# STIM300-carrierboard.net
KiCad netlist of a schematic drawn in Altium Designer
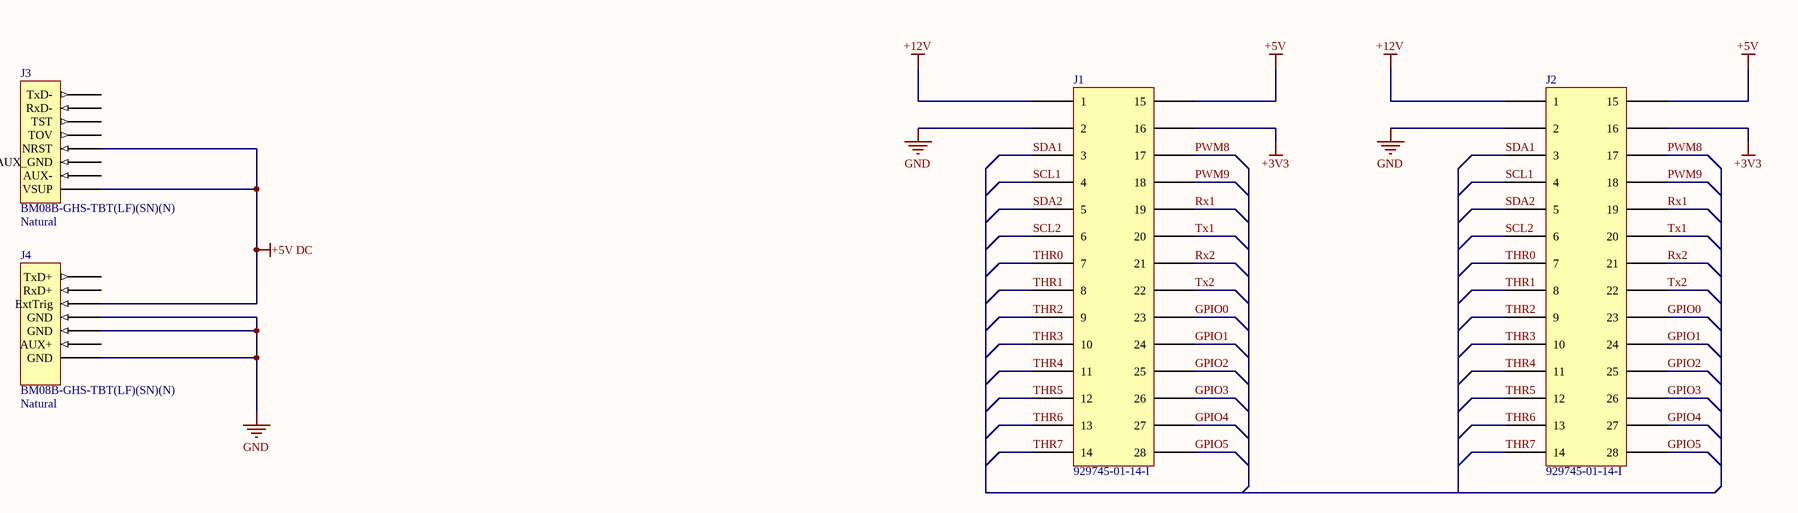
[diagram p0: STIM300-carrierboard.SchDoc]

(export (version "E")
  (design (tool "Eeschema 10.0.6"))
  (components
    (comp (ref "J1")
      (value "929745-01-14-I")
      (footprint "Header_14x2_RA")
      (libsource (lib "Vortex-component-database") (part "Header 14x2 RA"))
    )
    (comp (ref "J2")
      (value "929745-01-14-I")
      (footprint "Header_14x2_RA")
      (libsource (lib "Vortex-component-database") (part "Header 14x2 RA"))
    )
    (comp (ref "J3")
      (value "BM08B-GHS-TBT(LF)(SN)(N)")
      (footprint "JST BM08B-GHS-TBT")
      (description "CONN HEADER GH TOP 8POS 1.25MM")
      (fields (field (name "COLOUR") "Natural") (field (name "MANUFACTURER") "JST Sales America Inc."))
      (libsource (lib "Celestial Library Database") (part "8 Pin"))
    )
    (comp (ref "J4")
      (value "BM08B-GHS-TBT(LF)(SN)(N)")
      (footprint "JST BM08B-GHS-TBT")
      (description "CONN HEADER GH TOP 8POS 1.25MM")
      (fields (field (name "COLOUR") "Natural") (field (name "MANUFACTURER") "JST Sales America Inc."))
      (libsource (lib "Celestial Library Database") (part "8 Pin"))
    )
  )
  (nets
    (net (code "1") (name "+3V3") (class "Default")
      (node (ref "J1") (pin "16") (pinfunction "16_16") (pintype "passive"))
      (node (ref "J2") (pin "16") (pinfunction "16_16") (pintype "passive"))
    )
    (net (code "2") (name "+5V") (class "Default")
      (node (ref "J1") (pin "15") (pinfunction "15_15") (pintype "passive"))
      (node (ref "J2") (pin "15") (pinfunction "15_15") (pintype "passive"))
    )
    (net (code "3") (name "+5V DC") (class "Default")
      (node (ref "J3") (pin "5") (pinfunction "NRST_5") (pintype "input"))
      (node (ref "J3") (pin "8") (pinfunction "VSUP_8") (pintype "power_in"))
      (node (ref "J4") (pin "3") (pinfunction "TST_3") (pintype "output"))
    )
    (net (code "4") (name "+12V") (class "Default")
      (node (ref "J1") (pin "1") (pinfunction "1_1") (pintype "passive"))
      (node (ref "J2") (pin "1") (pinfunction "1_1") (pintype "passive"))
    )
    (net (code "5") (name "/GPIO0") (class "Default")
      (node (ref "J1") (pin "23") (pinfunction "23_23") (pintype "passive"))
      (node (ref "J2") (pin "23") (pinfunction "23_23") (pintype "passive"))
    )
    (net (code "6") (name "/GPIO1") (class "Default")
      (node (ref "J1") (pin "24") (pinfunction "24_24") (pintype "passive"))
      (node (ref "J2") (pin "24") (pinfunction "24_24") (pintype "passive"))
    )
    (net (code "7") (name "/GPIO2") (class "Default")
      (node (ref "J1") (pin "25") (pinfunction "25_25") (pintype "passive"))
      (node (ref "J2") (pin "25") (pinfunction "25_25") (pintype "passive"))
    )
    (net (code "8") (name "/GPIO3") (class "Default")
      (node (ref "J1") (pin "26") (pinfunction "26_26") (pintype "passive"))
      (node (ref "J2") (pin "26") (pinfunction "26_26") (pintype "passive"))
    )
    (net (code "9") (name "/GPIO4") (class "Default")
      (node (ref "J1") (pin "27") (pinfunction "27_27") (pintype "passive"))
      (node (ref "J2") (pin "27") (pinfunction "27_27") (pintype "passive"))
    )
    (net (code "10") (name "/GPIO5") (class "Default")
      (node (ref "J1") (pin "28") (pinfunction "28_28") (pintype "passive"))
      (node (ref "J2") (pin "28") (pinfunction "28_28") (pintype "passive"))
    )
    (net (code "11") (name "/PWM8") (class "Default")
      (node (ref "J1") (pin "17") (pinfunction "17_17") (pintype "passive"))
      (node (ref "J2") (pin "17") (pinfunction "17_17") (pintype "passive"))
    )
    (net (code "12") (name "/PWM9") (class "Default")
      (node (ref "J1") (pin "18") (pinfunction "18_18") (pintype "passive"))
      (node (ref "J2") (pin "18") (pinfunction "18_18") (pintype "passive"))
    )
    (net (code "13") (name "/Rx1") (class "Default")
      (node (ref "J1") (pin "19") (pinfunction "19_19") (pintype "passive"))
      (node (ref "J2") (pin "19") (pinfunction "19_19") (pintype "passive"))
    )
    (net (code "14") (name "/Rx2") (class "Default")
      (node (ref "J1") (pin "21") (pinfunction "21_21") (pintype "passive"))
      (node (ref "J2") (pin "21") (pinfunction "21_21") (pintype "passive"))
    )
    (net (code "15") (name "/SCL1") (class "Default")
      (node (ref "J1") (pin "4") (pinfunction "4_4") (pintype "passive"))
      (node (ref "J2") (pin "4") (pinfunction "4_4") (pintype "passive"))
    )
    (net (code "16") (name "/SCL2") (class "Default")
      (node (ref "J1") (pin "6") (pinfunction "6_6") (pintype "passive"))
      (node (ref "J2") (pin "6") (pinfunction "6_6") (pintype "passive"))
    )
    (net (code "17") (name "/SDA1") (class "Default")
      (node (ref "J1") (pin "3") (pinfunction "3_3") (pintype "passive"))
      (node (ref "J2") (pin "3") (pinfunction "3_3") (pintype "passive"))
    )
    (net (code "18") (name "/SDA2") (class "Default")
      (node (ref "J1") (pin "5") (pinfunction "5_5") (pintype "passive"))
      (node (ref "J2") (pin "5") (pinfunction "5_5") (pintype "passive"))
    )
    (net (code "19") (name "/THR0") (class "Default")
      (node (ref "J1") (pin "7") (pinfunction "7_7") (pintype "passive"))
      (node (ref "J2") (pin "7") (pinfunction "7_7") (pintype "passive"))
    )
    (net (code "20") (name "/THR1") (class "Default")
      (node (ref "J1") (pin "8") (pinfunction "8_8") (pintype "passive"))
      (node (ref "J2") (pin "8") (pinfunction "8_8") (pintype "passive"))
    )
    (net (code "21") (name "/THR2") (class "Default")
      (node (ref "J1") (pin "9") (pinfunction "9_9") (pintype "passive"))
      (node (ref "J2") (pin "9") (pinfunction "9_9") (pintype "passive"))
    )
    (net (code "22") (name "/THR3") (class "Default")
      (node (ref "J1") (pin "10") (pinfunction "10_10") (pintype "passive"))
      (node (ref "J2") (pin "10") (pinfunction "10_10") (pintype "passive"))
    )
    (net (code "23") (name "/THR4") (class "Default")
      (node (ref "J1") (pin "11") (pinfunction "11_11") (pintype "passive"))
      (node (ref "J2") (pin "11") (pinfunction "11_11") (pintype "passive"))
    )
    (net (code "24") (name "/THR5") (class "Default")
      (node (ref "J1") (pin "12") (pinfunction "12_12") (pintype "passive"))
      (node (ref "J2") (pin "12") (pinfunction "12_12") (pintype "passive"))
    )
    (net (code "25") (name "/THR6") (class "Default")
      (node (ref "J1") (pin "13") (pinfunction "13_13") (pintype "passive"))
      (node (ref "J2") (pin "13") (pinfunction "13_13") (pintype "passive"))
    )
    (net (code "26") (name "/THR7") (class "Default")
      (node (ref "J1") (pin "14") (pinfunction "14_14") (pintype "passive"))
      (node (ref "J2") (pin "14") (pinfunction "14_14") (pintype "passive"))
    )
    (net (code "27") (name "/Tx1") (class "Default")
      (node (ref "J1") (pin "20") (pinfunction "20_20") (pintype "passive"))
      (node (ref "J2") (pin "20") (pinfunction "20_20") (pintype "passive"))
    )
    (net (code "28") (name "/Tx2") (class "Default")
      (node (ref "J1") (pin "22") (pinfunction "22_22") (pintype "passive"))
      (node (ref "J2") (pin "22") (pinfunction "22_22") (pintype "passive"))
    )
    (net (code "29") (name "GND") (class "Default")
      (node (ref "J1") (pin "2") (pinfunction "2_2") (pintype "passive"))
      (node (ref "J2") (pin "2") (pinfunction "2_2") (pintype "passive"))
      (node (ref "J4") (pin "4") (pinfunction "TOV_4") (pintype "output"))
      (node (ref "J4") (pin "5") (pinfunction "NRST_5") (pintype "input"))
      (node (ref "J4") (pin "7") (pinfunction "AUX-_7") (pintype "input"))
    )
    (net (code "30") (name "unconnected-(J3-AUX--Pad7)") (class "Default")
      (node (ref "J3") (pin "7") (pinfunction "AUX-_7") (pintype "input"))
    )
    (net (code "31") (name "unconnected-(J3-AUX_GND-Pad6)") (class "Default")
      (node (ref "J3") (pin "6") (pinfunction "AUX_GND_6") (pintype "input"))
    )
    (net (code "32") (name "unconnected-(J3-RxD--Pad2)") (class "Default")
      (node (ref "J3") (pin "2") (pinfunction "RxD-_2") (pintype "input"))
    )
    (net (code "33") (name "unconnected-(J3-TOV-Pad4)") (class "Default")
      (node (ref "J3") (pin "4") (pinfunction "TOV_4") (pintype "output"))
    )
    (net (code "34") (name "unconnected-(J3-TST-Pad3)") (class "Default")
      (node (ref "J3") (pin "3") (pinfunction "TST_3") (pintype "output"))
    )
    (net (code "35") (name "unconnected-(J3-TxD--Pad1)") (class "Default")
      (node (ref "J3") (pin "1") (pinfunction "TxD-_1") (pintype "output"))
    )
    (net (code "36") (name "unconnected-(J4-AUX_GND-Pad6)") (class "Default")
      (node (ref "J4") (pin "6") (pinfunction "AUX_GND_6") (pintype "input"))
    )
    (net (code "37") (name "unconnected-(J4-RxD--Pad2)") (class "Default")
      (node (ref "J4") (pin "2") (pinfunction "RxD-_2") (pintype "input"))
    )
    (net (code "38") (name "unconnected-(J4-TxD--Pad1)") (class "Default")
      (node (ref "J4") (pin "1") (pinfunction "TxD-_1") (pintype "output"))
    )
    (net (code "39") (name "unconnected-(J4-VSUP-Pad8)") (class "Default")
      (node (ref "J4") (pin "8") (pinfunction "VSUP_8") (pintype "power_in"))
    )
  )
)
